# Output_Schematic.net
KiCad netlist of a schematic drawn in Altium Designer
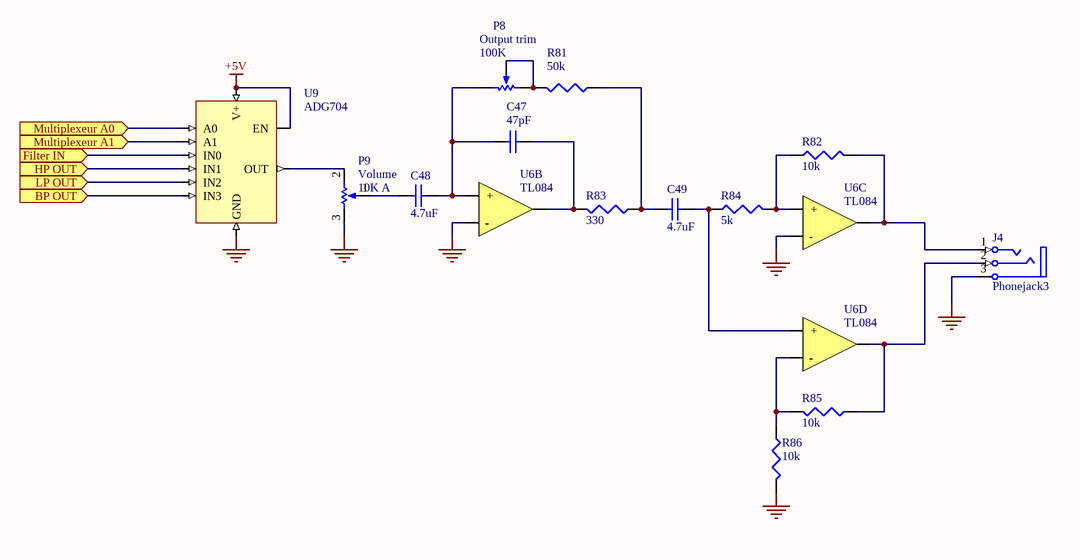
[diagram p0: Output.Schematic.SchDoc]

(export (version "E")
  (design (tool "Eeschema 10.0.6"))
  (components
    (comp (ref "C47")
      (value "47pF")
      (footprint "CAPC1608N - cap")
      (description "Capacitor (Semiconductor SIM Model)")
      (fields (field (name "PUBLISHER") "Altium Limited"))
      (libsource (lib "Miscellaneous Devices") (part "Cap Semi"))
    )
    (comp (ref "C48")
      (value "4.7uF")
      (footprint "CAPC1608N - cap")
      (description "Capacitor (Semiconductor SIM Model)")
      (fields (field (name "PUBLISHER") "Altium Limited"))
      (libsource (lib "Miscellaneous Devices") (part "Cap Semi"))
    )
    (comp (ref "C49")
      (value "4.7uF")
      (footprint "CAPC1608N - cap")
      (description "Capacitor (Semiconductor SIM Model)")
      (fields (field (name "PUBLISHER") "Altium Limited"))
      (libsource (lib "Miscellaneous Devices") (part "Cap Semi"))
    )
    (comp (ref "J4")
      (value "Phonejack3")
      (footprint "Header 3")
      (description "Jack Socket, 1/4\" [6.5mm], Thru-Hole, Vertical, 3-Conductor Open Circuit (Non-Normalling)")
      (fields (field (name "PUBLISHER") "Altium Limited"))
      (libsource (lib "Miscellaneous Connectors") (part "Phonejack3"))
    )
    (comp (ref "P8")
      (value "Output trim")
      (footprint "BOURNS Trim pot")
      (description "Potentiometer")
      (fields (field (name "ALTIUM_VALUE") "100K") (field (name "PUBLISHER") "Altium Limited"))
      (libsource (lib "") (part "RPot_1"))
    )
    (comp (ref "P9")
      (value "Volume")
      (footprint "ALPS Potentiometer")
      (description "Potentiometer")
      (fields (field (name "ALTIUM_VALUE") "10K A") (field (name "PUBLISHER") "Altium Limited"))
      (libsource (lib "Miscellaneous Devices") (part "RPot"))
    )
    (comp (ref "R81")
      (value "50k")
      (footprint "CAPC1608N")
      (description "Resistor")
      (fields (field (name "PUBLISHER") "Altium Limited"))
      (libsource (lib "Miscellaneous Devices") (part "Res3"))
    )
    (comp (ref "R82")
      (value "10k")
      (footprint "CAPC1608N")
      (description "Resistor")
      (fields (field (name "PUBLISHER") "Altium Limited"))
      (libsource (lib "Miscellaneous Devices") (part "Res3"))
    )
    (comp (ref "R83")
      (value "330")
      (footprint "CAPC1608N")
      (description "Resistor")
      (fields (field (name "PUBLISHER") "Altium Limited"))
      (libsource (lib "Miscellaneous Devices") (part "Res3"))
    )
    (comp (ref "R84")
      (value "5k")
      (footprint "CAPC1608N")
      (description "Resistor")
      (fields (field (name "PUBLISHER") "Altium Limited"))
      (libsource (lib "Miscellaneous Devices") (part "Res3"))
    )
    (comp (ref "R85")
      (value "10k")
      (footprint "CAPC1608N")
      (description "Resistor")
      (fields (field (name "PUBLISHER") "Altium Limited"))
      (libsource (lib "Miscellaneous Devices") (part "Res3"))
    )
    (comp (ref "R86")
      (value "10k")
      (footprint "CAPC1608N")
      (description "Resistor")
      (fields (field (name "PUBLISHER") "Altium Limited"))
      (libsource (lib "Miscellaneous Devices") (part "Res3"))
    )
    (comp (ref "U6B")
      (value "TL084")
      (footprint "TL084 - 3pads")
      (libsource (lib "SynthyTwo.Components") (part "TL084"))
    )
    (comp (ref "U6C")
      (value "TL084")
      (footprint "TL084 - 3pads")
      (libsource (lib "SynthyTwo.Components") (part "TL084"))
    )
    (comp (ref "U6D")
      (value "TL084")
      (footprint "TL084 - 3pads")
      (libsource (lib "SynthyTwo.Components") (part "TL084"))
    )
    (comp (ref "U9")
      (value "ADG704")
      (footprint "ADG704")
      (libsource (lib "SynthyTwo.Components") (part "ADG704"))
    )
  )
  (nets
    (net (code "1") (name "+5V") (class "Default")
      (node (ref "U9") (pin "5") (pinfunction "EN_5") (pintype "passive"))
      (node (ref "U9") (pin "6") (pinfunction "V+_6") (pintype "input"))
    )
    (net (code "2") (name "/BP OUT") (class "Default")
      (node (ref "U9") (pin "7") (pinfunction "IN3_7") (pintype "input"))
    )
    (net (code "3") (name "/Filter IN") (class "Default")
      (node (ref "U9") (pin "2") (pinfunction "IN0_2") (pintype "input"))
    )
    (net (code "4") (name "/HP OUT") (class "Default")
      (node (ref "U9") (pin "9") (pinfunction "IN1_9") (pintype "input"))
    )
    (net (code "5") (name "/LP OUT") (class "Default")
      (node (ref "U9") (pin "4") (pinfunction "IN2_4") (pintype "input"))
    )
    (net (code "6") (name "/Multiplexeur A0") (class "Default")
      (node (ref "U9") (pin "1") (pinfunction "A0_1") (pintype "input"))
    )
    (net (code "7") (name "/Multiplexeur A1") (class "Default")
      (node (ref "U9") (pin "10") (pinfunction "A1_10") (pintype "input"))
    )
    (net (code "8") (name "GND") (class "Default")
      (node (ref "J4") (pin "3") (pinfunction "S_3") (pintype "power_in"))
      (node (ref "P9") (pin "3") (pinfunction "TOP_3") (pintype "passive"))
      (node (ref "R86") (pin "2") (pinfunction "2_2") (pintype "passive"))
      (node (ref "U6B") (pin "2") (pinfunction "-_2") (pintype "passive"))
      (node (ref "U6C") (pin "2") (pinfunction "-_2") (pintype "passive"))
      (node (ref "U9") (pin "3") (pinfunction "GND_3") (pintype "input"))
    )
    (net (code "9") (name "Net-(C49-Pad1)") (class "Default")
      (node (ref "C49") (pin "1") (pinfunction "1_1") (pintype "passive"))
      (node (ref "R81") (pin "1") (pinfunction "1_1") (pintype "passive"))
      (node (ref "R83") (pin "1") (pinfunction "1_1") (pintype "passive"))
    )
    (net (code "10") (name "Net-(J4-R)") (class "Default")
      (node (ref "J4") (pin "2") (pinfunction "R_2") (pintype "input"))
      (node (ref "R85") (pin "1") (pinfunction "1_1") (pintype "passive"))
      (node (ref "U6D") (pin "1") (pinfunction "OUT_1") (pintype "passive"))
    )
    (net (code "11") (name "Net-(J4-T)") (class "Default")
      (node (ref "J4") (pin "1") (pinfunction "T_1") (pintype "input"))
      (node (ref "R82") (pin "2") (pinfunction "2_2") (pintype "passive"))
      (node (ref "U6C") (pin "1") (pinfunction "OUT_1") (pintype "passive"))
    )
    (net (code "12") (name "Net-(P8-BOT)") (class "Default")
      (node (ref "P8") (pin "2") (pinfunction "BOT_2") (pintype "passive"))
      (node (ref "P8") (pin "3") (pinfunction "TAP_3") (pintype "passive"))
      (node (ref "R81") (pin "2") (pinfunction "2_2") (pintype "passive"))
    )
    (net (code "13") (name "Net-(P8-TOP)") (class "Default")
      (node (ref "C47") (pin "1") (pinfunction "1_1") (pintype "passive"))
      (node (ref "C48") (pin "2") (pinfunction "2_2") (pintype "passive"))
      (node (ref "P8") (pin "1") (pinfunction "TOP_1") (pintype "passive"))
      (node (ref "U6B") (pin "3") (pinfunction "+_3") (pintype "passive"))
    )
    (net (code "14") (name "Net-(P9-BOT)") (class "Default")
      (node (ref "P9") (pin "2") (pinfunction "BOT_2") (pintype "passive"))
      (node (ref "U9") (pin "8") (pinfunction "OUT_8") (pintype "output"))
    )
    (net (code "15") (name "Net-(P9-TAP)") (class "Default")
      (node (ref "C48") (pin "1") (pinfunction "1_1") (pintype "passive"))
      (node (ref "P9") (pin "1") (pinfunction "TAP_1") (pintype "passive"))
    )
    (net (code "16") (name "Net-(U6B-OUT)") (class "Default")
      (node (ref "C47") (pin "2") (pinfunction "2_2") (pintype "passive"))
      (node (ref "R83") (pin "2") (pinfunction "2_2") (pintype "passive"))
      (node (ref "U6B") (pin "1") (pinfunction "OUT_1") (pintype "passive"))
    )
    (net (code "17") (name "Net-(U6C-+)") (class "Default")
      (node (ref "R82") (pin "1") (pinfunction "1_1") (pintype "passive"))
      (node (ref "R84") (pin "2") (pinfunction "2_2") (pintype "passive"))
      (node (ref "U6C") (pin "3") (pinfunction "+_3") (pintype "passive"))
    )
    (net (code "18") (name "Net-(U6D-+)") (class "Default")
      (node (ref "C49") (pin "2") (pinfunction "2_2") (pintype "passive"))
      (node (ref "R84") (pin "1") (pinfunction "1_1") (pintype "passive"))
      (node (ref "U6D") (pin "3") (pinfunction "+_3") (pintype "passive"))
    )
    (net (code "19") (name "Net-(U6D--)") (class "Default")
      (node (ref "R85") (pin "2") (pinfunction "2_2") (pintype "passive"))
      (node (ref "R86") (pin "1") (pinfunction "1_1") (pintype "passive"))
      (node (ref "U6D") (pin "2") (pinfunction "-_2") (pintype "passive"))
    )
  )
)
